# SCH_Revised_Dice_Roller_2023-06-08.net
KiCad netlist of a schematic drawn in EasyEDA
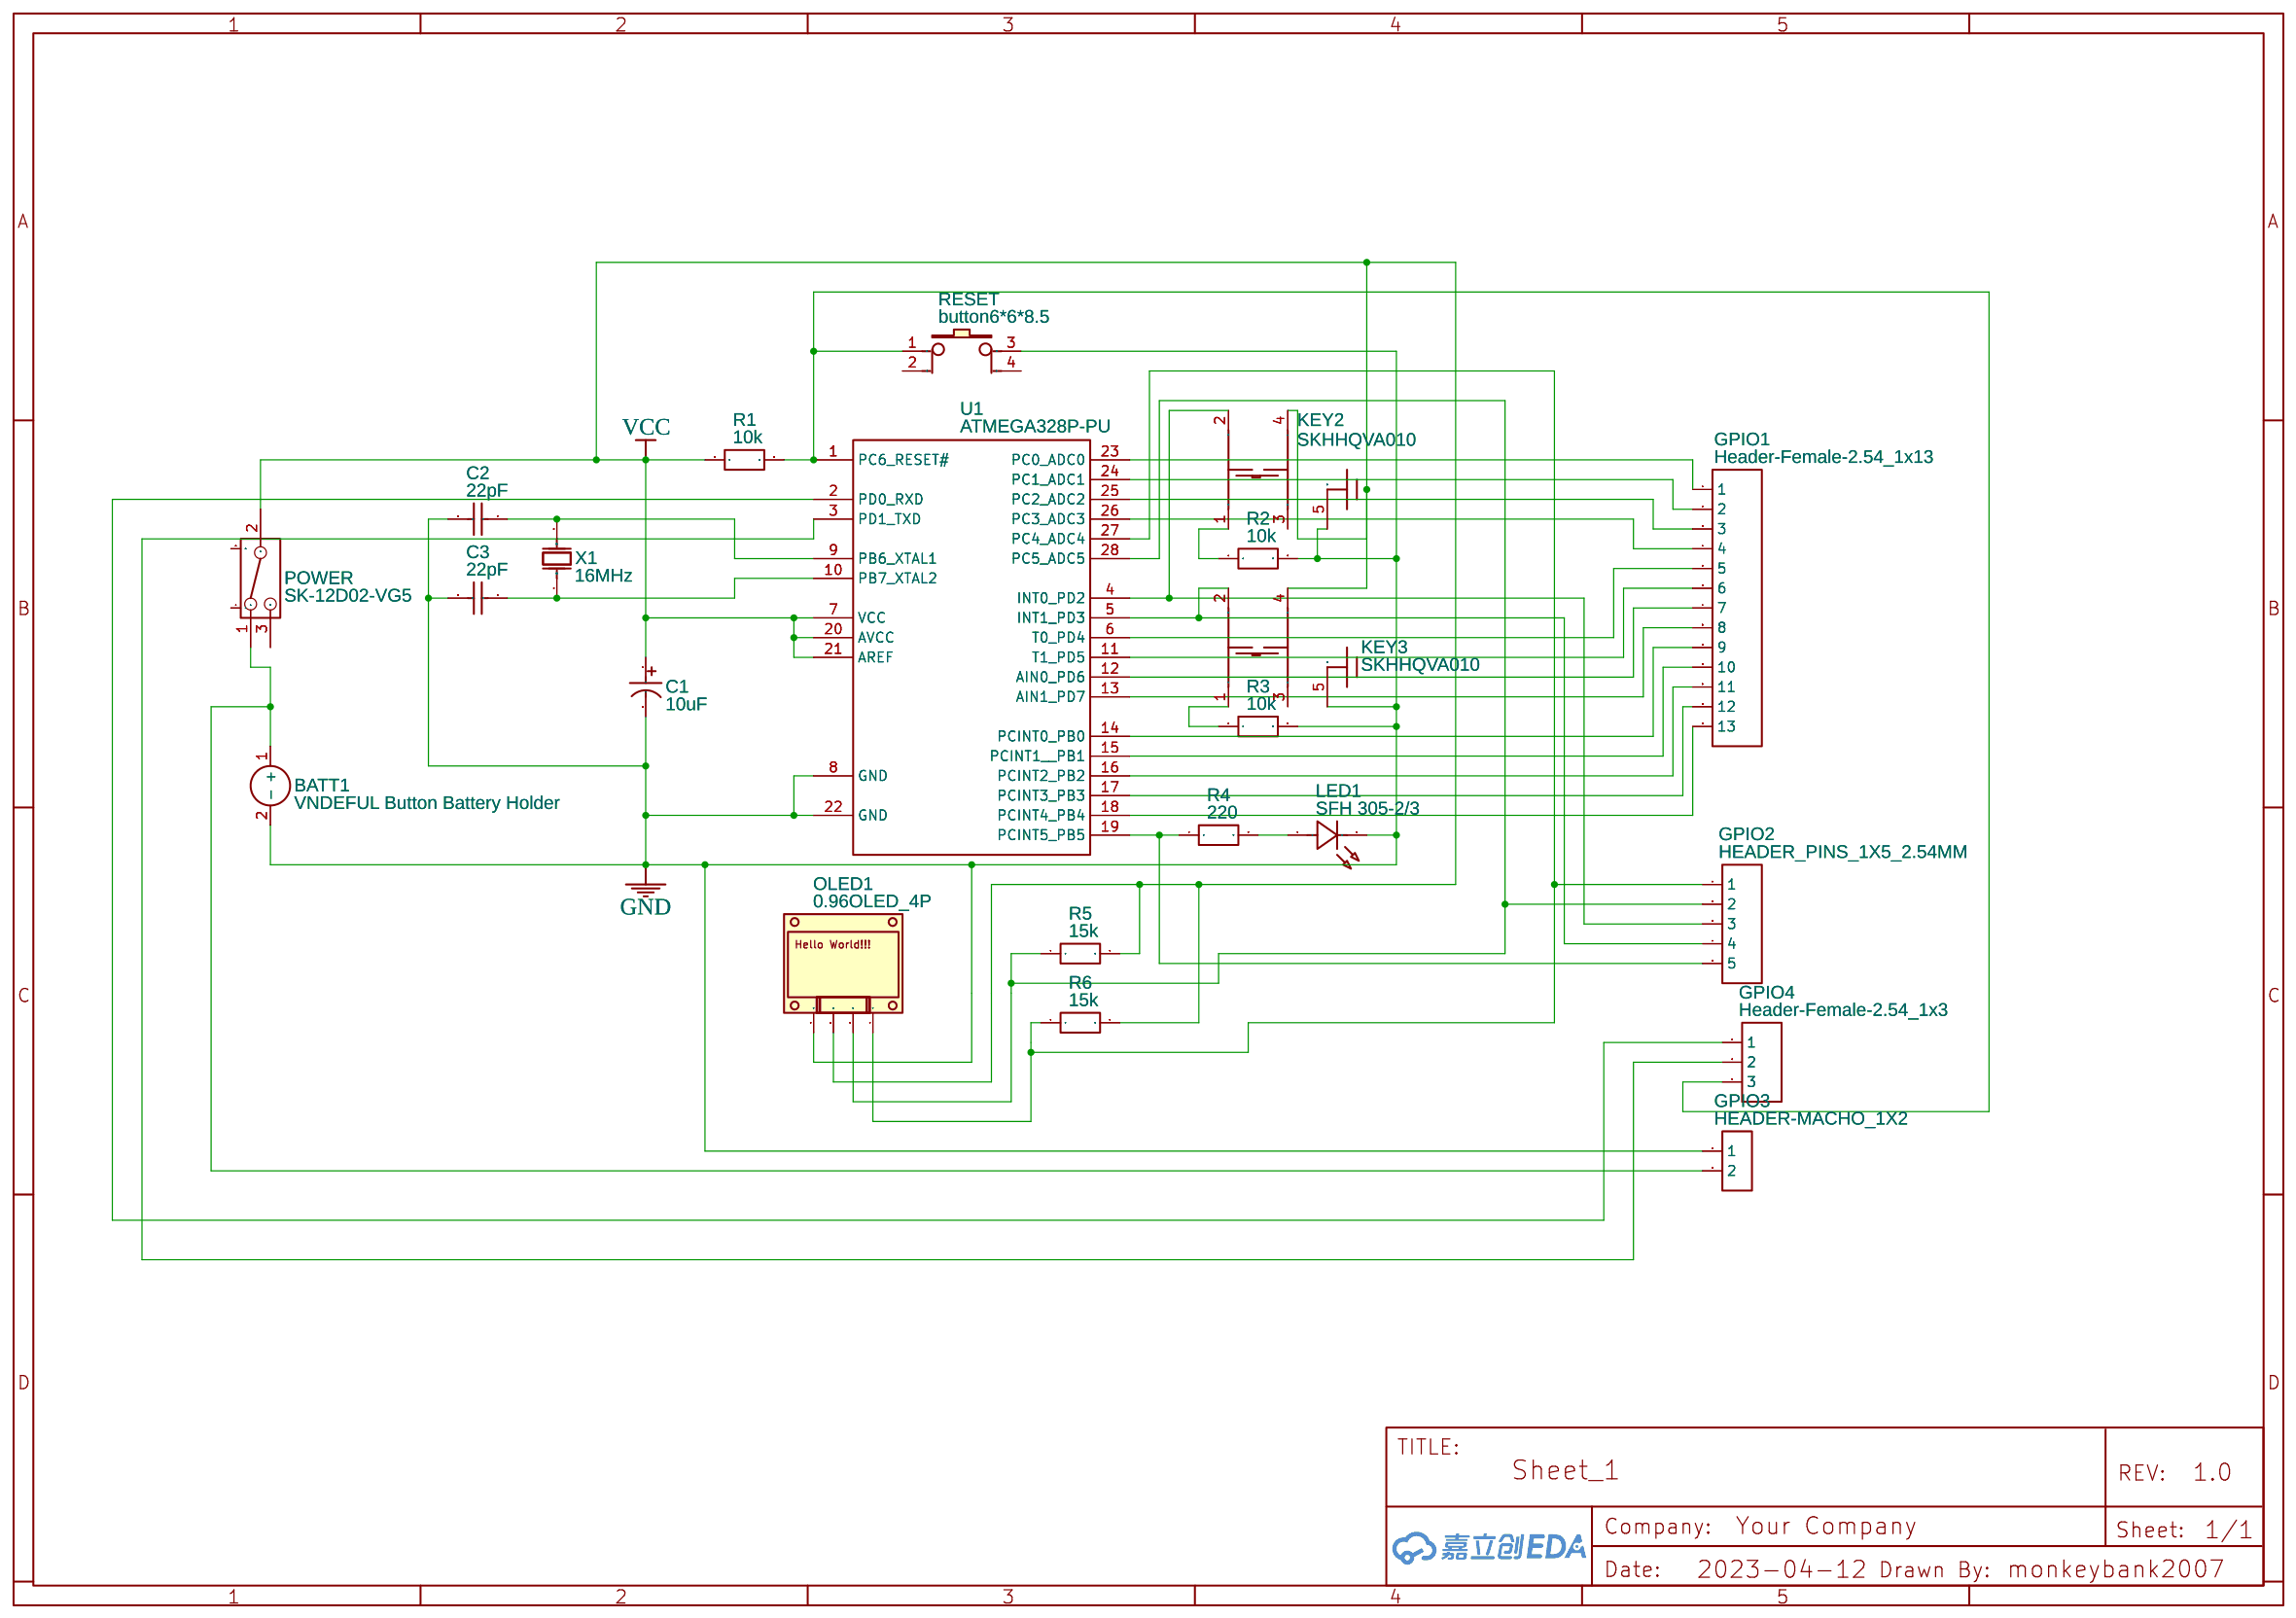
[diagram p0: schematic sheet]

(export (version "E")
  (design (tool "Eeschema 10.0.6"))
  (components
    (comp (ref "BATT1")
      (value "VNDEFUL Button Battery Holder")
      (fields (field (name "BOM_Supplier Part") "B01J5FY2GI"))
      (libsource (lib "") (part "VNDEFUL Button Battery Holder"))
    )
    (comp (ref "C1")
      (value "10uF")
      (fields
        (field (name "BOM_Manufacturer Part") "KS106M050C07RR0VH2FP0")
        (field (name "BOM_Supplier Part") "C32856")
      )
      (libsource (lib "") (part "electrolytic capacitor10UF50V"))
    )
    (comp (ref "C2")
      (value "22pF")
      (fields
        (field (name "BOM_Manufacturer Part") "Calibration capacitor22NF（223） 100V 5%")
        (field (name "BOM_Supplier Part") "C26612")
      )
      (libsource (lib "") (part "Calibration capacitor22NF（223） 100V 5%"))
    )
    (comp (ref "C3")
      (value "22pF")
      (fields
        (field (name "BOM_Manufacturer Part") "Calibration capacitor22NF（223） 100V 5%")
        (field (name "BOM_Supplier Part") "C26612")
      )
      (libsource (lib "") (part "Calibration capacitor22NF（223） 100V 5%"))
    )
    (comp (ref "GPIO1")
      (value "Header-Female-2.54_1x13")
      (fields
        (field (name "BOM_Manufacturer Part") "2.54-1*13P母")
        (field (name "BOM_Supplier Part") "C52709")
      )
      (libsource (lib "") (part "Header-Female-2.54_1x13"))
    )
    (comp (ref "GPIO2") (value "HEADER_PINS_1X5_2.54MM") (libsource (lib "") (part "HEADER_PINS_1X5_2.54MM")))
    (comp (ref "GPIO3")
      (value "HEADER-MACHO_1X2")
      (fields
        (field (name "BOM_Manufacturer Part") "Header-Female-2.54_1x4")
        (field (name "BOM_Supplier Part") "C124413")
      )
      (libsource (lib "") (part "HEADER-MACHO_1X2"))
    )
    (comp (ref "GPIO4")
      (value "Header-Female-2.54_1x3")
      (fields
        (field (name "BOM_Manufacturer Part") "2.54-1*3P母")
        (field (name "BOM_Supplier Part") "C146243")
      )
      (libsource (lib "") (part "Header-Female-2.54_1x3"))
    )
    (comp (ref "KEY2")
      (value "SKHHQVA010")
      (fields (field (name "BOM_Supplier Part") "C470256"))
      (libsource (lib "") (part "SKHHQVA010"))
    )
    (comp (ref "KEY3")
      (value "SKHHQVA010")
      (fields (field (name "BOM_Supplier Part") "C470256"))
      (libsource (lib "") (part "SKHHQVA010"))
    )
    (comp (ref "LED1")
      (value "SFH 305-2/3")
      (fields (field (name "BOM_Supplier Part") "C2900246"))
      (libsource (lib "") (part "SFH 305-2/3"))
    )
    (comp (ref "OLED1") (value "0.96OLED_4P") (libsource (lib "") (part "0.96OLED_4P")))
    (comp (ref "POWER")
      (value "SK-12D02-VG5")
      (fields (field (name "BOM_Supplier Part") "C136722"))
      (libsource (lib "") (part "SK-12D02-VG5"))
    )
    (comp (ref "R1")
      (value "10k")
      (fields
        (field (name "BOM_Manufacturer Part") "PNP300JR-73-0R22")
        (field (name "BOM_Supplier Part") "C1742268")
      )
      (libsource (lib "") (part "PNP300JR-73-0R22"))
    )
    (comp (ref "R2")
      (value "10k")
      (fields
        (field (name "BOM_Manufacturer Part") "PNP300JR-73-0R22")
        (field (name "BOM_Supplier Part") "C1742268")
      )
      (libsource (lib "") (part "PNP300JR-73-0R22"))
    )
    (comp (ref "R3")
      (value "10k")
      (fields
        (field (name "BOM_Manufacturer Part") "PNP300JR-73-0R22")
        (field (name "BOM_Supplier Part") "C1742268")
      )
      (libsource (lib "") (part "PNP300JR-73-0R22"))
    )
    (comp (ref "R4")
      (value "220")
      (fields
        (field (name "BOM_Manufacturer Part") "PNP300JR-73-0R22")
        (field (name "BOM_Supplier Part") "C1742268")
      )
      (libsource (lib "") (part "PNP300JR-73-0R22"))
    )
    (comp (ref "R5")
      (value "15k")
      (fields
        (field (name "BOM_Manufacturer Part") "PNP300JR-73-0R22")
        (field (name "BOM_Supplier Part") "C1742268")
      )
      (libsource (lib "") (part "PNP300JR-73-0R22"))
    )
    (comp (ref "R6")
      (value "15k")
      (fields
        (field (name "BOM_Manufacturer Part") "PNP300JR-73-0R22")
        (field (name "BOM_Supplier Part") "C1742268")
      )
      (libsource (lib "") (part "PNP300JR-73-0R22"))
    )
    (comp (ref "RESET")
      (value "button6*6*8.5")
      (fields (field (name "BOM_Supplier Part") "C59980"))
      (libsource (lib "") (part "button6*6*8.5"))
    )
    (comp (ref "U1")
      (value "ATMEGA328P-PU")
      (fields (field (name "BOM_Supplier Part") "C33901"))
      (libsource (lib "") (part "ATMEGA328P-PU"))
    )
    (comp (ref "X1")
      (value "16MHz")
      (fields
        (field (name "BOM_Manufacturer Part") "49SAC20000202040")
        (field (name "BOM_Supplier Part") "C443544")
      )
      (libsource (lib "") (part "49SAC20000202040"))
    )
  )
  (nets
    (net (code "1") (name "GND") (class "Default")
      (node (ref "BATT1") (pin "2") (pinfunction "-_2") (pintype "unspecified"))
      (node (ref "C1") (pin "2") (pinfunction "-_2") (pintype "input"))
      (node (ref "C2") (pin "1") (pinfunction "1_1") (pintype "input"))
      (node (ref "C3") (pin "1") (pinfunction "1_1") (pintype "input"))
      (node (ref "GPIO3") (pin "1") (pinfunction "1_1") (pintype "input"))
      (node (ref "KEY2") (pin "5") (pinfunction "5_5") (pintype "unspecified"))
      (node (ref "KEY3") (pin "5") (pinfunction "5_5") (pintype "unspecified"))
      (node (ref "LED1") (pin "2") (pinfunction "K_2") (pintype "unspecified"))
      (node (ref "OLED1") (pin "1") (pinfunction "1_1") (pintype "unspecified"))
      (node (ref "R2") (pin "2") (pinfunction "2_2") (pintype "unspecified"))
      (node (ref "R3") (pin "2") (pinfunction "2_2") (pintype "unspecified"))
      (node (ref "RESET") (pin "3") (pinfunction "3_3") (pintype "input"))
      (node (ref "U1") (pin "22") (pinfunction "GND_22") (pintype "passive"))
      (node (ref "U1") (pin "8") (pinfunction "GND_8") (pintype "passive"))
    )
    (net (code "2") (name "Net-(BATT1-+)") (class "Default")
      (node (ref "BATT1") (pin "1") (pinfunction "+_1") (pintype "unspecified"))
      (node (ref "GPIO3") (pin "2") (pinfunction "2_2") (pintype "input"))
      (node (ref "POWER") (pin "1") (pinfunction "1_1") (pintype "unspecified"))
    )
    (net (code "3") (name "Net-(KEY2-Pad1)") (class "Default")
      (node (ref "KEY2") (pin "1") (pinfunction "1_1") (pintype "unspecified"))
      (node (ref "R2") (pin "1") (pinfunction "1_1") (pintype "unspecified"))
    )
    (net (code "4") (name "Net-(KEY3-Pad1)") (class "Default")
      (node (ref "KEY3") (pin "1") (pinfunction "1_1") (pintype "unspecified"))
      (node (ref "R3") (pin "1") (pinfunction "1_1") (pintype "unspecified"))
    )
    (net (code "5") (name "Net-(LED1-A)") (class "Default")
      (node (ref "LED1") (pin "1") (pinfunction "A_1") (pintype "unspecified"))
      (node (ref "R4") (pin "2") (pinfunction "2_2") (pintype "unspecified"))
    )
    (net (code "6") (name "Net-(U1-AIN0_PD6)") (class "Default")
      (node (ref "GPIO1") (pin "7") (pinfunction "7_7") (pintype "input"))
      (node (ref "U1") (pin "12") (pinfunction "AIN0_PD6_12") (pintype "bidirectional"))
    )
    (net (code "7") (name "Net-(U1-AIN1_PD7)") (class "Default")
      (node (ref "GPIO1") (pin "8") (pinfunction "8_8") (pintype "input"))
      (node (ref "U1") (pin "13") (pinfunction "AIN1_PD7_13") (pintype "bidirectional"))
    )
    (net (code "8") (name "Net-(U1-INT0_PD2)") (class "Default")
      (node (ref "GPIO2") (pin "3") (pinfunction "3_3") (pintype "input"))
      (node (ref "KEY2") (pin "2") (pinfunction "2_2") (pintype "unspecified"))
      (node (ref "U1") (pin "4") (pinfunction "INT0_PD2_4") (pintype "bidirectional"))
    )
    (net (code "9") (name "Net-(U1-INT1_PD3)") (class "Default")
      (node (ref "GPIO2") (pin "4") (pinfunction "4_4") (pintype "input"))
      (node (ref "KEY3") (pin "2") (pinfunction "2_2") (pintype "unspecified"))
      (node (ref "U1") (pin "5") (pinfunction "INT1_PD3_5") (pintype "bidirectional"))
    )
    (net (code "10") (name "Net-(U1-PB6_XTAL1)") (class "Default")
      (node (ref "C2") (pin "2") (pinfunction "2_2") (pintype "input"))
      (node (ref "U1") (pin "9") (pinfunction "PB6_XTAL1_9") (pintype "bidirectional"))
      (node (ref "X1") (pin "2") (pinfunction "OSC2_2") (pintype "input"))
    )
    (net (code "11") (name "Net-(U1-PB7_XTAL2)") (class "Default")
      (node (ref "C3") (pin "2") (pinfunction "2_2") (pintype "input"))
      (node (ref "U1") (pin "10") (pinfunction "PB7_XTAL2_10") (pintype "bidirectional"))
      (node (ref "X1") (pin "1") (pinfunction "OSC1_1") (pintype "input"))
    )
    (net (code "12") (name "Net-(U1-PC0_ADC0)") (class "Default")
      (node (ref "GPIO1") (pin "1") (pinfunction "1_1") (pintype "input"))
      (node (ref "U1") (pin "23") (pinfunction "PC0_ADC0_23") (pintype "bidirectional"))
    )
    (net (code "13") (name "Net-(U1-PC1_ADC1)") (class "Default")
      (node (ref "GPIO1") (pin "2") (pinfunction "2_2") (pintype "input"))
      (node (ref "U1") (pin "24") (pinfunction "PC1_ADC1_24") (pintype "bidirectional"))
    )
    (net (code "14") (name "Net-(U1-PC2_ADC2)") (class "Default")
      (node (ref "GPIO1") (pin "3") (pinfunction "3_3") (pintype "input"))
      (node (ref "U1") (pin "25") (pinfunction "PC2_ADC2_25") (pintype "bidirectional"))
    )
    (net (code "15") (name "Net-(U1-PC3_ADC3)") (class "Default")
      (node (ref "GPIO1") (pin "4") (pinfunction "4_4") (pintype "input"))
      (node (ref "U1") (pin "26") (pinfunction "PC3_ADC3_26") (pintype "bidirectional"))
    )
    (net (code "16") (name "Net-(U1-PC4_ADC4)") (class "Default")
      (node (ref "GPIO2") (pin "1") (pinfunction "1_1") (pintype "input"))
      (node (ref "OLED1") (pin "4") (pinfunction "4_4") (pintype "unspecified"))
      (node (ref "R6") (pin "1") (pinfunction "1_1") (pintype "unspecified"))
      (node (ref "U1") (pin "27") (pinfunction "PC4_ADC4_27") (pintype "bidirectional"))
    )
    (net (code "17") (name "Net-(U1-PC5_ADC5)") (class "Default")
      (node (ref "GPIO2") (pin "2") (pinfunction "2_2") (pintype "input"))
      (node (ref "OLED1") (pin "3") (pinfunction "3_3") (pintype "unspecified"))
      (node (ref "R5") (pin "1") (pinfunction "1_1") (pintype "unspecified"))
      (node (ref "U1") (pin "28") (pinfunction "PC5_ADC5_28") (pintype "bidirectional"))
    )
    (net (code "18") (name "Net-(U1-PC6_RESET#)") (class "Default")
      (node (ref "GPIO4") (pin "3") (pinfunction "3_3") (pintype "input"))
      (node (ref "R1") (pin "2") (pinfunction "2_2") (pintype "unspecified"))
      (node (ref "RESET") (pin "1") (pinfunction "1_1") (pintype "input"))
      (node (ref "U1") (pin "1") (pinfunction "PC6_RESET#_1") (pintype "bidirectional"))
    )
    (net (code "19") (name "Net-(U1-PCINT0_PB0)") (class "Default")
      (node (ref "GPIO1") (pin "9") (pinfunction "9_9") (pintype "input"))
      (node (ref "U1") (pin "14") (pinfunction "PCINT0_PB0_14") (pintype "bidirectional"))
    )
    (net (code "20") (name "Net-(U1-PCINT1__PB1)") (class "Default")
      (node (ref "GPIO1") (pin "10") (pinfunction "10_10") (pintype "input"))
      (node (ref "U1") (pin "15") (pinfunction "PCINT1__PB1_15") (pintype "bidirectional"))
    )
    (net (code "21") (name "Net-(U1-PCINT2_PB2)") (class "Default")
      (node (ref "GPIO1") (pin "11") (pinfunction "11_11") (pintype "input"))
      (node (ref "U1") (pin "16") (pinfunction "PCINT2_PB2_16") (pintype "bidirectional"))
    )
    (net (code "22") (name "Net-(U1-PCINT3_PB3)") (class "Default")
      (node (ref "GPIO1") (pin "12") (pinfunction "12_12") (pintype "input"))
      (node (ref "U1") (pin "17") (pinfunction "PCINT3_PB3_17") (pintype "bidirectional"))
    )
    (net (code "23") (name "Net-(U1-PCINT4_PB4)") (class "Default")
      (node (ref "GPIO1") (pin "13") (pinfunction "13_13") (pintype "input"))
      (node (ref "U1") (pin "18") (pinfunction "PCINT4_PB4_18") (pintype "bidirectional"))
    )
    (net (code "24") (name "Net-(U1-PCINT5_PB5)") (class "Default")
      (node (ref "GPIO2") (pin "5") (pinfunction "5_5") (pintype "input"))
      (node (ref "R4") (pin "1") (pinfunction "1_1") (pintype "unspecified"))
      (node (ref "U1") (pin "19") (pinfunction "PCINT5_PB5_19") (pintype "bidirectional"))
    )
    (net (code "25") (name "Net-(U1-PD0_RXD)") (class "Default")
      (node (ref "GPIO4") (pin "1") (pinfunction "1_1") (pintype "input"))
      (node (ref "U1") (pin "2") (pinfunction "PD0_RXD_2") (pintype "bidirectional"))
    )
    (net (code "26") (name "Net-(U1-PD1_TXD)") (class "Default")
      (node (ref "GPIO4") (pin "2") (pinfunction "2_2") (pintype "input"))
      (node (ref "U1") (pin "3") (pinfunction "PD1_TXD_3") (pintype "bidirectional"))
    )
    (net (code "27") (name "Net-(U1-T0_PD4)") (class "Default")
      (node (ref "GPIO1") (pin "5") (pinfunction "5_5") (pintype "input"))
      (node (ref "U1") (pin "6") (pinfunction "T0_PD4_6") (pintype "bidirectional"))
    )
    (net (code "28") (name "Net-(U1-T1_PD5)") (class "Default")
      (node (ref "GPIO1") (pin "6") (pinfunction "6_6") (pintype "input"))
      (node (ref "U1") (pin "11") (pinfunction "T1_PD5_11") (pintype "bidirectional"))
    )
    (net (code "29") (name "VCC") (class "Default")
      (node (ref "C1") (pin "1") (pinfunction "+_1") (pintype "input"))
      (node (ref "KEY2") (pin "4") (pinfunction "4_4") (pintype "unspecified"))
      (node (ref "KEY3") (pin "4") (pinfunction "4_4") (pintype "unspecified"))
      (node (ref "OLED1") (pin "2") (pinfunction "2_2") (pintype "unspecified"))
      (node (ref "POWER") (pin "2") (pinfunction "2_2") (pintype "unspecified"))
      (node (ref "R1") (pin "1") (pinfunction "1_1") (pintype "unspecified"))
      (node (ref "R5") (pin "2") (pinfunction "2_2") (pintype "unspecified"))
      (node (ref "R6") (pin "2") (pinfunction "2_2") (pintype "unspecified"))
      (node (ref "U1") (pin "20") (pinfunction "AVCC_20") (pintype "passive"))
      (node (ref "U1") (pin "21") (pinfunction "AREF_21") (pintype "passive"))
      (node (ref "U1") (pin "7") (pinfunction "VCC_7") (pintype "passive"))
    )
    (net (code "30") (name "unconnected-(KEY2-Pad3)") (class "Default")
      (node (ref "KEY2") (pin "3") (pinfunction "3_3") (pintype "unspecified"))
    )
    (net (code "31") (name "unconnected-(KEY3-Pad3)") (class "Default")
      (node (ref "KEY3") (pin "3") (pinfunction "3_3") (pintype "unspecified"))
    )
    (net (code "32") (name "unconnected-(POWER-Pad3)") (class "Default")
      (node (ref "POWER") (pin "3") (pinfunction "3_3") (pintype "unspecified"))
    )
    (net (code "33") (name "unconnected-(POWER-Pad4)") (class "Default")
      (node (ref "POWER") (pin "4") (pinfunction "4_4") (pintype "unspecified"))
    )
    (net (code "34") (name "unconnected-(POWER-Pad5)") (class "Default")
      (node (ref "POWER") (pin "5") (pinfunction "5_5") (pintype "unspecified"))
    )
    (net (code "35") (name "unconnected-(RESET-Pad2)") (class "Default")
      (node (ref "RESET") (pin "2") (pinfunction "2_2") (pintype "input"))
    )
    (net (code "36") (name "unconnected-(RESET-Pad4)") (class "Default")
      (node (ref "RESET") (pin "4") (pinfunction "4_4") (pintype "input"))
    )
  )
)
